# ESC.net
KiCad netlist of a schematic drawn in EAGLE
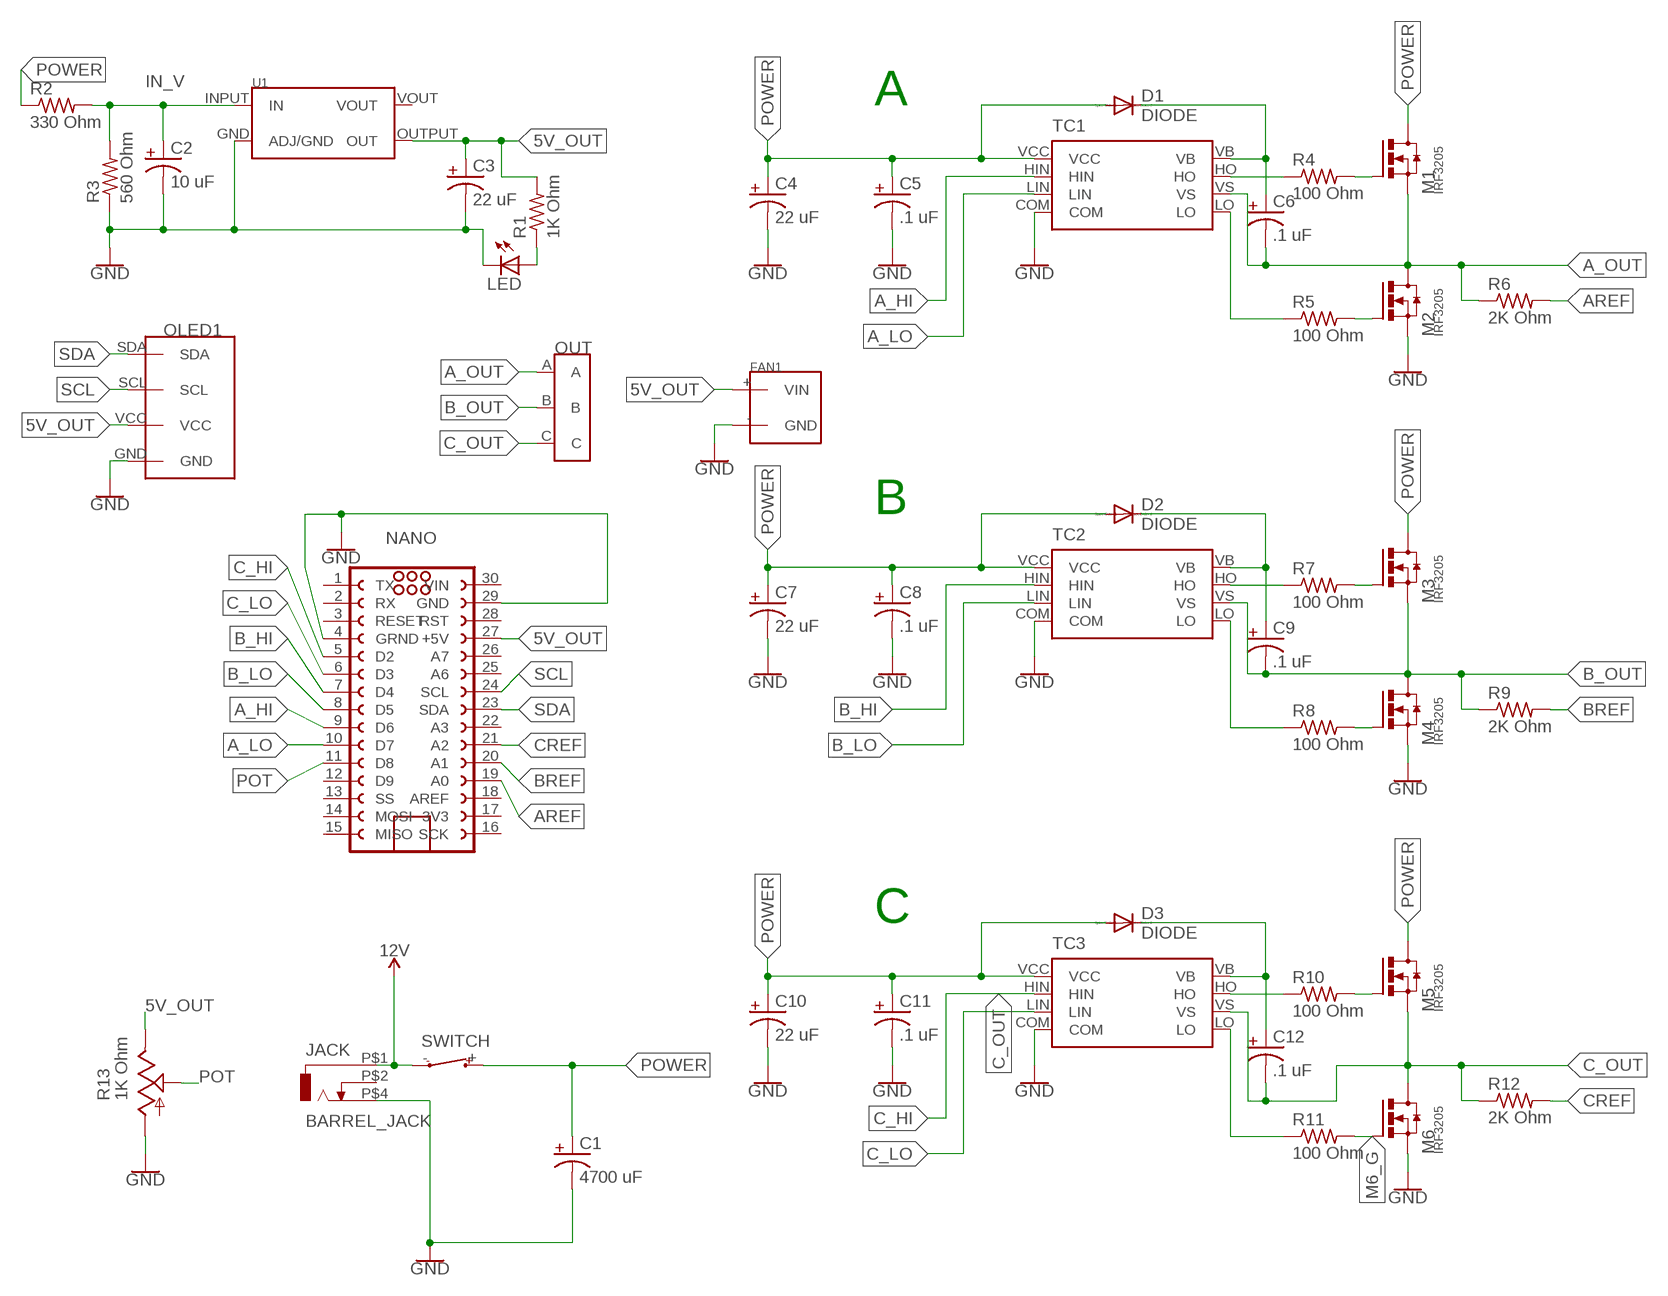
[diagram p0: schematic, sheet 1]

(export (version "E")
  (design (tool "Eeschema 10.0.6"))
  (components
    (comp (ref "C1")
      (value "4700 uF")
      (footprint "eagle-import:CAP_LARGE")
      (libsource (lib "eagle-import") (part "CAPACITORLARGE"))
    )
    (comp (ref "C2")
      (value "10 uF")
      (footprint "eagle-import:0805")
      (libsource (lib "eagle-import") (part "CAPACITOR"))
    )
    (comp (ref "C3")
      (value "22 uF")
      (footprint "eagle-import:0805")
      (libsource (lib "eagle-import") (part "CAPACITOR"))
    )
    (comp (ref "C4")
      (value "22 uF")
      (footprint "eagle-import:0805")
      (libsource (lib "eagle-import") (part "CAPACITOR"))
    )
    (comp (ref "C5")
      (value ".1 uF")
      (footprint "eagle-import:0805")
      (libsource (lib "eagle-import") (part "CAPACITOR"))
    )
    (comp (ref "C6")
      (value ".1 uF")
      (footprint "eagle-import:0805")
      (libsource (lib "eagle-import") (part "CAPACITOR"))
    )
    (comp (ref "C7")
      (value "22 uF")
      (footprint "eagle-import:0805")
      (libsource (lib "eagle-import") (part "CAPACITOR"))
    )
    (comp (ref "C8")
      (value ".1 uF")
      (footprint "eagle-import:0805")
      (libsource (lib "eagle-import") (part "CAPACITOR"))
    )
    (comp (ref "C9")
      (value ".1 uF")
      (footprint "eagle-import:0805")
      (libsource (lib "eagle-import") (part "CAPACITOR"))
    )
    (comp (ref "C10")
      (value "22 uF")
      (footprint "eagle-import:0805")
      (libsource (lib "eagle-import") (part "CAPACITOR"))
    )
    (comp (ref "C11")
      (value ".1 uF")
      (footprint "eagle-import:0805")
      (libsource (lib "eagle-import") (part "CAPACITOR"))
    )
    (comp (ref "C12")
      (value ".1 uF")
      (footprint "eagle-import:0805")
      (libsource (lib "eagle-import") (part "CAPACITOR"))
    )
    (comp (ref "D1")
      (value "DIODE")
      (footprint "eagle-import:DIODE")
      (libsource (lib "eagle-import") (part "DIODE"))
    )
    (comp (ref "D2")
      (value "DIODE")
      (footprint "eagle-import:DIODE")
      (libsource (lib "eagle-import") (part "DIODE"))
    )
    (comp (ref "D3")
      (value "DIODE")
      (footprint "eagle-import:DIODE")
      (libsource (lib "eagle-import") (part "DIODE"))
    )
    (comp (ref "FAN1")
      (value "2P_POWER")
      (footprint "eagle-import:2P_POWER")
      (libsource (lib "eagle-import") (part "2P_POWER"))
    )
    (comp (ref "JACK")
      (value "BARREL_JACK")
      (footprint "eagle-import:BARREL_JACK")
      (libsource (lib "eagle-import") (part "BARREL_JACK"))
    )
    (comp (ref "LED")
      (value "LED")
      (footprint "eagle-import:LED_PADS")
      (libsource (lib "eagle-import") (part "LED"))
    )
    (comp (ref "M1")
      (value "IRF3205")
      (footprint "eagle-import:IRF3205")
      (libsource (lib "eagle-import") (part "IRF3205"))
    )
    (comp (ref "M2")
      (value "IRF3205")
      (footprint "eagle-import:IRF3205")
      (libsource (lib "eagle-import") (part "IRF3205"))
    )
    (comp (ref "M3")
      (value "IRF3205")
      (footprint "eagle-import:IRF3205")
      (libsource (lib "eagle-import") (part "IRF3205"))
    )
    (comp (ref "M4")
      (value "IRF3205")
      (footprint "eagle-import:IRF3205")
      (libsource (lib "eagle-import") (part "IRF3205"))
    )
    (comp (ref "M5")
      (value "IRF3205")
      (footprint "eagle-import:IRF3205")
      (libsource (lib "eagle-import") (part "IRF3205"))
    )
    (comp (ref "M6")
      (value "IRF3205")
      (footprint "eagle-import:IRF3205")
      (libsource (lib "eagle-import") (part "IRF3205"))
    )
    (comp (ref "NANO")
      (value "ARDUINO_NANO_CONNECTOR")
      (footprint "eagle-import:ARDUINO_NANO_HEADER")
      (libsource (lib "eagle-import") (part "ARDUINO_NANO_CONNECTOR"))
    )
    (comp (ref "OLED1")
      (value "I2C_OLED_4PIN_HEADER")
      (footprint "eagle-import:OLED_CONNECTION")
      (libsource (lib "eagle-import") (part "I2C_OLED_4PIN_HEADER"))
    )
    (comp (ref "OUT")
      (value "TERMINAL3")
      (footprint "eagle-import:3PIN_TERMINAL")
      (libsource (lib "eagle-import") (part "TERMINAL3"))
    )
    (comp (ref "R1")
      (value "1K Ohm")
      (footprint "eagle-import:0805")
      (libsource (lib "eagle-import") (part "RESISTOR0805"))
    )
    (comp (ref "R2")
      (value "330 Ohm")
      (footprint "eagle-import:RESISTOR")
      (libsource (lib "eagle-import") (part "RESISTOR"))
    )
    (comp (ref "R3")
      (value "560 Ohm")
      (footprint "eagle-import:RESISTOR")
      (libsource (lib "eagle-import") (part "RESISTOR"))
    )
    (comp (ref "R4")
      (value "100 Ohm")
      (footprint "eagle-import:0805")
      (libsource (lib "eagle-import") (part "RESISTOR0805"))
    )
    (comp (ref "R5")
      (value "100 Ohm")
      (footprint "eagle-import:0805")
      (libsource (lib "eagle-import") (part "RESISTOR0805"))
    )
    (comp (ref "R6")
      (value "2K Ohm")
      (footprint "eagle-import:0805")
      (libsource (lib "eagle-import") (part "RESISTOR0805"))
    )
    (comp (ref "R7")
      (value "100 Ohm")
      (footprint "eagle-import:0805")
      (libsource (lib "eagle-import") (part "RESISTOR0805"))
    )
    (comp (ref "R8")
      (value "100 Ohm")
      (footprint "eagle-import:0805")
      (libsource (lib "eagle-import") (part "RESISTOR0805"))
    )
    (comp (ref "R9")
      (value "2K Ohm")
      (footprint "eagle-import:0805")
      (libsource (lib "eagle-import") (part "RESISTOR0805"))
    )
    (comp (ref "R10")
      (value "100 Ohm")
      (footprint "eagle-import:0805")
      (libsource (lib "eagle-import") (part "RESISTOR0805"))
    )
    (comp (ref "R11")
      (value "100 Ohm")
      (footprint "eagle-import:0805")
      (libsource (lib "eagle-import") (part "RESISTOR0805"))
    )
    (comp (ref "R12")
      (value "2K Ohm")
      (footprint "eagle-import:0805")
      (libsource (lib "eagle-import") (part "RESISTOR0805"))
    )
    (comp (ref "R13")
      (value "1K Ohm")
      (footprint "eagle-import:POT")
      (libsource (lib "eagle-import") (part "POT"))
    )
    (comp (ref "SWITCH")
      (value "BOAT_SWITCH")
      (footprint "eagle-import:2P_POWER")
      (libsource (lib "eagle-import") (part "BOAT_SWITCH"))
    )
    (comp (ref "TC1")
      (value "TSC428CPA")
      (footprint "eagle-import:PDIP-8_N")
      (libsource (lib "eagle-import") (part "TSC428CPA"))
    )
    (comp (ref "TC2")
      (value "TSC428CPA")
      (footprint "eagle-import:PDIP-8_N")
      (libsource (lib "eagle-import") (part "TSC428CPA"))
    )
    (comp (ref "TC3")
      (value "TSC428CPA")
      (footprint "eagle-import:PDIP-8_N")
      (libsource (lib "eagle-import") (part "TSC428CPA"))
    )
    (comp (ref "U1")
      (value "AZ1117CH")
      (footprint "eagle-import:AZ1117CH")
      (libsource (lib "eagle-import") (part "AZ1117CH"))
    )
  )
  (nets
    (net (code "1") (name "/3V3") (class "Default")
      (node (ref "NANO") (pin "17") (pinfunction "3V3_17") (pintype "power_in"))
    )
    (net (code "2") (name "/IN_V") (class "Default")
      (node (ref "C2") (pin "1") (pinfunction "ANODE_1") (pintype "passive"))
      (node (ref "R2") (pin "P$2") (pinfunction "2_P$2") (pintype "passive"))
      (node (ref "R3") (pin "P$2") (pinfunction "2_P$2") (pintype "passive"))
      (node (ref "U1") (pin "INPUT") (pinfunction "IN_INPUT") (pintype "power_in"))
    )
    (net (code "3") (name "5V_OUT") (class "Default")
      (node (ref "C3") (pin "1") (pinfunction "ANODE_1") (pintype "passive"))
      (node (ref "FAN1") (pin "+") (pinfunction "VIN_+") (pintype "power_in"))
      (node (ref "NANO") (pin "27") (pinfunction "+5V_27") (pintype "power_in"))
      (node (ref "OLED1") (pin "VCC") (pinfunction "VCC_VCC") (pintype "power_in"))
      (node (ref "R1") (pin "2") (pinfunction "2_2") (pintype "passive"))
      (node (ref "R13") (pin "+") (pinfunction "+_+") (pintype "passive"))
      (node (ref "U1") (pin "OUTPUT") (pinfunction "OUT_OUTPUT") (pintype "output"))
    )
    (net (code "4") (name "12V") (class "Default")
      (node (ref "JACK") (pin "P$1") (pinfunction "1_P$1") (pintype "passive"))
      (node (ref "SWITCH") (pin "-") (pinfunction "-_-") (pintype "passive"))
    )
    (net (code "5") (name "AREF") (class "Default")
      (node (ref "NANO") (pin "19") (pinfunction "A0_19") (pintype "bidirectional"))
      (node (ref "R6") (pin "2") (pinfunction "2_2") (pintype "passive"))
    )
    (net (code "6") (name "A_HI") (class "Default")
      (node (ref "NANO") (pin "9") (pinfunction "D6_9") (pintype "bidirectional"))
      (node (ref "TC1") (pin "HIN") (pinfunction "HIN_HIN") (pintype "input"))
    )
    (net (code "7") (name "A_LO") (class "Default")
      (node (ref "NANO") (pin "10") (pinfunction "D7_10") (pintype "bidirectional"))
      (node (ref "TC1") (pin "LIN") (pinfunction "LIN_LIN") (pintype "input"))
    )
    (net (code "8") (name "A_OUT") (class "Default")
      (node (ref "C6") (pin "2") (pinfunction "CATHODE_2") (pintype "passive"))
      (node (ref "M1") (pin "SOURCE") (pinfunction "S_SOURCE") (pintype "passive"))
      (node (ref "M2") (pin "DRAIN") (pinfunction "D_DRAIN") (pintype "passive"))
      (node (ref "OUT") (pin "A") (pinfunction "A_A") (pintype "bidirectional"))
      (node (ref "R6") (pin "1") (pinfunction "1_1") (pintype "passive"))
      (node (ref "TC1") (pin "VS") (pinfunction "VS_VS") (pintype "passive"))
    )
    (net (code "9") (name "BREF") (class "Default")
      (node (ref "NANO") (pin "20") (pinfunction "A1_20") (pintype "bidirectional"))
      (node (ref "R9") (pin "2") (pinfunction "2_2") (pintype "passive"))
    )
    (net (code "10") (name "B_HI") (class "Default")
      (node (ref "NANO") (pin "7") (pinfunction "D4_7") (pintype "bidirectional"))
      (node (ref "TC2") (pin "HIN") (pinfunction "HIN_HIN") (pintype "input"))
    )
    (net (code "11") (name "B_LO") (class "Default")
      (node (ref "NANO") (pin "8") (pinfunction "D5_8") (pintype "bidirectional"))
      (node (ref "TC2") (pin "LIN") (pinfunction "LIN_LIN") (pintype "input"))
    )
    (net (code "12") (name "B_OUT") (class "Default")
      (node (ref "C9") (pin "2") (pinfunction "CATHODE_2") (pintype "passive"))
      (node (ref "M3") (pin "SOURCE") (pinfunction "S_SOURCE") (pintype "passive"))
      (node (ref "M4") (pin "DRAIN") (pinfunction "D_DRAIN") (pintype "passive"))
      (node (ref "OUT") (pin "B") (pinfunction "B_B") (pintype "bidirectional"))
      (node (ref "R9") (pin "1") (pinfunction "1_1") (pintype "passive"))
      (node (ref "TC2") (pin "VS") (pinfunction "VS_VS") (pintype "passive"))
    )
    (net (code "13") (name "CREF") (class "Default")
      (node (ref "NANO") (pin "21") (pinfunction "A2_21") (pintype "bidirectional"))
      (node (ref "R12") (pin "2") (pinfunction "2_2") (pintype "passive"))
    )
    (net (code "14") (name "C_HI") (class "Default")
      (node (ref "NANO") (pin "5") (pinfunction "D2_5") (pintype "bidirectional"))
      (node (ref "TC3") (pin "HIN") (pinfunction "HIN_HIN") (pintype "input"))
    )
    (net (code "15") (name "C_LO") (class "Default")
      (node (ref "NANO") (pin "6") (pinfunction "D3_6") (pintype "bidirectional"))
      (node (ref "TC3") (pin "LIN") (pinfunction "LIN_LIN") (pintype "input"))
    )
    (net (code "16") (name "C_OUT") (class "Default")
      (node (ref "C12") (pin "2") (pinfunction "CATHODE_2") (pintype "passive"))
      (node (ref "M5") (pin "SOURCE") (pinfunction "S_SOURCE") (pintype "passive"))
      (node (ref "M6") (pin "DRAIN") (pinfunction "D_DRAIN") (pintype "passive"))
      (node (ref "OUT") (pin "C") (pinfunction "C_C") (pintype "bidirectional"))
      (node (ref "R12") (pin "1") (pinfunction "1_1") (pintype "passive"))
      (node (ref "TC3") (pin "VS") (pinfunction "VS_VS") (pintype "passive"))
    )
    (net (code "17") (name "GND") (class "Default")
      (node (ref "C1") (pin "CATHODE") (pinfunction "CATHODE_CATHODE") (pintype "passive"))
      (node (ref "C10") (pin "2") (pinfunction "CATHODE_2") (pintype "passive"))
      (node (ref "C11") (pin "2") (pinfunction "CATHODE_2") (pintype "passive"))
      (node (ref "C2") (pin "2") (pinfunction "CATHODE_2") (pintype "passive"))
      (node (ref "C3") (pin "2") (pinfunction "CATHODE_2") (pintype "passive"))
      (node (ref "C4") (pin "2") (pinfunction "CATHODE_2") (pintype "passive"))
      (node (ref "C5") (pin "2") (pinfunction "CATHODE_2") (pintype "passive"))
      (node (ref "C7") (pin "2") (pinfunction "CATHODE_2") (pintype "passive"))
      (node (ref "C8") (pin "2") (pinfunction "CATHODE_2") (pintype "passive"))
      (node (ref "FAN1") (pin "-") (pinfunction "GND_-") (pintype "power_in"))
      (node (ref "JACK") (pin "P$4") (pinfunction "3_P$4") (pintype "passive"))
      (node (ref "LED") (pin "C") (pinfunction "C_C") (pintype "passive"))
      (node (ref "M2") (pin "SOURCE") (pinfunction "S_SOURCE") (pintype "passive"))
      (node (ref "M4") (pin "SOURCE") (pinfunction "S_SOURCE") (pintype "passive"))
      (node (ref "M6") (pin "SOURCE") (pinfunction "S_SOURCE") (pintype "passive"))
      (node (ref "NANO") (pin "29") (pinfunction "GND_29") (pintype "power_in"))
      (node (ref "NANO") (pin "4") (pinfunction "GRND_4") (pintype "power_in"))
      (node (ref "OLED1") (pin "GND") (pinfunction "GND_GND") (pintype "power_in"))
      (node (ref "R13") (pin "-") (pinfunction "-_-") (pintype "passive"))
      (node (ref "R3") (pin "P$1") (pinfunction "1_P$1") (pintype "passive"))
      (node (ref "TC1") (pin "COM") (pinfunction "COM_COM") (pintype "input"))
      (node (ref "TC2") (pin "COM") (pinfunction "COM_COM") (pintype "input"))
      (node (ref "TC3") (pin "COM") (pinfunction "COM_COM") (pintype "input"))
      (node (ref "U1") (pin "GND") (pinfunction "ADJ/GND_GND") (pintype "bidirectional"))
    )
    (net (code "18") (name "M6_G") (class "Default")
      (node (ref "M6") (pin "GATE") (pinfunction "G_GATE") (pintype "passive"))
      (node (ref "R11") (pin "2") (pinfunction "2_2") (pintype "passive"))
    )
    (net (code "19") (name "Net-(C6-ANODE)") (class "Default")
      (node (ref "C6") (pin "1") (pinfunction "ANODE_1") (pintype "passive"))
      (node (ref "D1") (pin "C") (pinfunction "C_C") (pintype "passive"))
      (node (ref "TC1") (pin "VB") (pinfunction "VB_VB") (pintype "output"))
    )
    (net (code "20") (name "Net-(C9-ANODE)") (class "Default")
      (node (ref "C9") (pin "1") (pinfunction "ANODE_1") (pintype "passive"))
      (node (ref "D2") (pin "C") (pinfunction "C_C") (pintype "passive"))
      (node (ref "TC2") (pin "VB") (pinfunction "VB_VB") (pintype "output"))
    )
    (net (code "21") (name "Net-(C12-ANODE)") (class "Default")
      (node (ref "C12") (pin "1") (pinfunction "ANODE_1") (pintype "passive"))
      (node (ref "D3") (pin "C") (pinfunction "C_C") (pintype "passive"))
      (node (ref "TC3") (pin "VB") (pinfunction "VB_VB") (pintype "output"))
    )
    (net (code "22") (name "Net-(LED-PadA)") (class "Default")
      (node (ref "LED") (pin "A") (pinfunction "A_A") (pintype "passive"))
      (node (ref "R1") (pin "1") (pinfunction "1_1") (pintype "passive"))
    )
    (net (code "23") (name "Net-(M1-G)") (class "Default")
      (node (ref "M1") (pin "GATE") (pinfunction "G_GATE") (pintype "passive"))
      (node (ref "R4") (pin "2") (pinfunction "2_2") (pintype "passive"))
    )
    (net (code "24") (name "Net-(M2-G)") (class "Default")
      (node (ref "M2") (pin "GATE") (pinfunction "G_GATE") (pintype "passive"))
      (node (ref "R5") (pin "2") (pinfunction "2_2") (pintype "passive"))
    )
    (net (code "25") (name "Net-(M3-G)") (class "Default")
      (node (ref "M3") (pin "GATE") (pinfunction "G_GATE") (pintype "passive"))
      (node (ref "R7") (pin "2") (pinfunction "2_2") (pintype "passive"))
    )
    (net (code "26") (name "Net-(M4-G)") (class "Default")
      (node (ref "M4") (pin "GATE") (pinfunction "G_GATE") (pintype "passive"))
      (node (ref "R8") (pin "2") (pinfunction "2_2") (pintype "passive"))
    )
    (net (code "27") (name "Net-(M5-G)") (class "Default")
      (node (ref "M5") (pin "GATE") (pinfunction "G_GATE") (pintype "passive"))
      (node (ref "R10") (pin "2") (pinfunction "2_2") (pintype "passive"))
    )
    (net (code "28") (name "Net-(R4-Pad1)") (class "Default")
      (node (ref "R4") (pin "1") (pinfunction "1_1") (pintype "passive"))
      (node (ref "TC1") (pin "HO") (pinfunction "HO_HO") (pintype "output"))
    )
    (net (code "29") (name "Net-(R5-Pad1)") (class "Default")
      (node (ref "R5") (pin "1") (pinfunction "1_1") (pintype "passive"))
      (node (ref "TC1") (pin "LO") (pinfunction "LO_LO") (pintype "power_in"))
    )
    (net (code "30") (name "Net-(R7-Pad1)") (class "Default")
      (node (ref "R7") (pin "1") (pinfunction "1_1") (pintype "passive"))
      (node (ref "TC2") (pin "HO") (pinfunction "HO_HO") (pintype "output"))
    )
    (net (code "31") (name "Net-(R8-Pad1)") (class "Default")
      (node (ref "R8") (pin "1") (pinfunction "1_1") (pintype "passive"))
      (node (ref "TC2") (pin "LO") (pinfunction "LO_LO") (pintype "power_in"))
    )
    (net (code "32") (name "Net-(R10-Pad1)") (class "Default")
      (node (ref "R10") (pin "1") (pinfunction "1_1") (pintype "passive"))
      (node (ref "TC3") (pin "HO") (pinfunction "HO_HO") (pintype "output"))
    )
    (net (code "33") (name "Net-(R11-Pad1)") (class "Default")
      (node (ref "R11") (pin "1") (pinfunction "1_1") (pintype "passive"))
      (node (ref "TC3") (pin "LO") (pinfunction "LO_LO") (pintype "power_in"))
    )
    (net (code "34") (name "POT") (class "Default")
      (node (ref "NANO") (pin "11") (pinfunction "D8_11") (pintype "bidirectional"))
      (node (ref "R13") (pin "VAR") (pinfunction "VAR_VAR") (pintype "passive"))
    )
    (net (code "35") (name "POWER") (class "Default")
      (node (ref "C1") (pin "ANODE") (pinfunction "ANODE_ANODE") (pintype "passive"))
      (node (ref "C10") (pin "1") (pinfunction "ANODE_1") (pintype "passive"))
      (node (ref "C11") (pin "1") (pinfunction "ANODE_1") (pintype "passive"))
      (node (ref "C4") (pin "1") (pinfunction "ANODE_1") (pintype "passive"))
      (node (ref "C5") (pin "1") (pinfunction "ANODE_1") (pintype "passive"))
      (node (ref "C7") (pin "1") (pinfunction "ANODE_1") (pintype "passive"))
      (node (ref "C8") (pin "1") (pinfunction "ANODE_1") (pintype "passive"))
      (node (ref "D1") (pin "A") (pinfunction "A_A") (pintype "passive"))
      (node (ref "D2") (pin "A") (pinfunction "A_A") (pintype "passive"))
      (node (ref "D3") (pin "A") (pinfunction "A_A") (pintype "passive"))
      (node (ref "M1") (pin "DRAIN") (pinfunction "D_DRAIN") (pintype "passive"))
      (node (ref "M3") (pin "DRAIN") (pinfunction "D_DRAIN") (pintype "passive"))
      (node (ref "M5") (pin "DRAIN") (pinfunction "D_DRAIN") (pintype "passive"))
      (node (ref "R2") (pin "P$1") (pinfunction "1_P$1") (pintype "passive"))
      (node (ref "SWITCH") (pin "+") (pinfunction "+_+") (pintype "passive"))
      (node (ref "TC1") (pin "VCC") (pinfunction "VCC_VCC") (pintype "input"))
      (node (ref "TC2") (pin "VCC") (pinfunction "VCC_VCC") (pintype "input"))
      (node (ref "TC3") (pin "VCC") (pinfunction "VCC_VCC") (pintype "input"))
    )
    (net (code "36") (name "SCL") (class "Default")
      (node (ref "NANO") (pin "24") (pinfunction "SCL_24") (pintype "output"))
      (node (ref "OLED1") (pin "SCL") (pinfunction "SCL_SCL") (pintype "bidirectional"))
    )
    (net (code "37") (name "SDA") (class "Default")
      (node (ref "NANO") (pin "23") (pinfunction "SDA_23") (pintype "output"))
      (node (ref "OLED1") (pin "SDA") (pinfunction "SDA_SDA") (pintype "bidirectional"))
    )
    (net (code "38") (name "unconnected-(JACK-2-PadP$2)") (class "Default")
      (node (ref "JACK") (pin "P$2") (pinfunction "2_P$2") (pintype "passive"))
    )
    (net (code "39") (name "unconnected-(NANO-A3-Pad22)") (class "Default")
      (node (ref "NANO") (pin "22") (pinfunction "A3_22") (pintype "bidirectional"))
    )
    (net (code "40") (name "unconnected-(NANO-A6-Pad25)") (class "Default")
      (node (ref "NANO") (pin "25") (pinfunction "A6_25") (pintype "bidirectional"))
    )
    (net (code "41") (name "unconnected-(NANO-A7-Pad26)") (class "Default")
      (node (ref "NANO") (pin "26") (pinfunction "A7_26") (pintype "bidirectional"))
    )
    (net (code "42") (name "unconnected-(NANO-AREF-Pad18)") (class "Default")
      (node (ref "NANO") (pin "18") (pinfunction "AREF_18") (pintype "bidirectional"))
    )
    (net (code "43") (name "unconnected-(NANO-D9-Pad12)") (class "Default")
      (node (ref "NANO") (pin "12") (pinfunction "D9_12") (pintype "bidirectional"))
    )
    (net (code "44") (name "unconnected-(NANO-MISO-Pad15)") (class "Default")
      (node (ref "NANO") (pin "15") (pinfunction "MISO_15") (pintype "bidirectional"))
    )
    (net (code "45") (name "unconnected-(NANO-MOSI-Pad14)") (class "Default")
      (node (ref "NANO") (pin "14") (pinfunction "MOSI_14") (pintype "bidirectional"))
    )
    (net (code "46") (name "unconnected-(NANO-RESET-Pad3)") (class "Default")
      (node (ref "NANO") (pin "3") (pinfunction "RESET_3") (pintype "bidirectional"))
    )
    (net (code "47") (name "unconnected-(NANO-RST-Pad28)") (class "Default")
      (node (ref "NANO") (pin "28") (pinfunction "RST_28") (pintype "bidirectional"))
    )
    (net (code "48") (name "unconnected-(NANO-RX-Pad2)") (class "Default")
      (node (ref "NANO") (pin "2") (pinfunction "RX_2") (pintype "bidirectional"))
    )
    (net (code "49") (name "unconnected-(NANO-SCK-Pad16)") (class "Default")
      (node (ref "NANO") (pin "16") (pinfunction "SCK_16") (pintype "bidirectional"))
    )
    (net (code "50") (name "unconnected-(NANO-SS-Pad13)") (class "Default")
      (node (ref "NANO") (pin "13") (pinfunction "SS_13") (pintype "bidirectional"))
    )
    (net (code "51") (name "unconnected-(NANO-TX-Pad1)") (class "Default")
      (node (ref "NANO") (pin "1") (pinfunction "TX_1") (pintype "bidirectional"))
    )
    (net (code "52") (name "unconnected-(NANO-VIN-Pad30)") (class "Default")
      (node (ref "NANO") (pin "30") (pinfunction "VIN_30") (pintype "input"))
    )
    (net (code "53") (name "unconnected-(U1-PadVOUT)") (class "Default")
      (node (ref "U1") (pin "VOUT") (pinfunction "VOUT_VOUT") (pintype "bidirectional"))
    )
  )
)
